# 5v_negative_and_positive_channels.net
KiCad netlist of a schematic drawn in Altium Designer
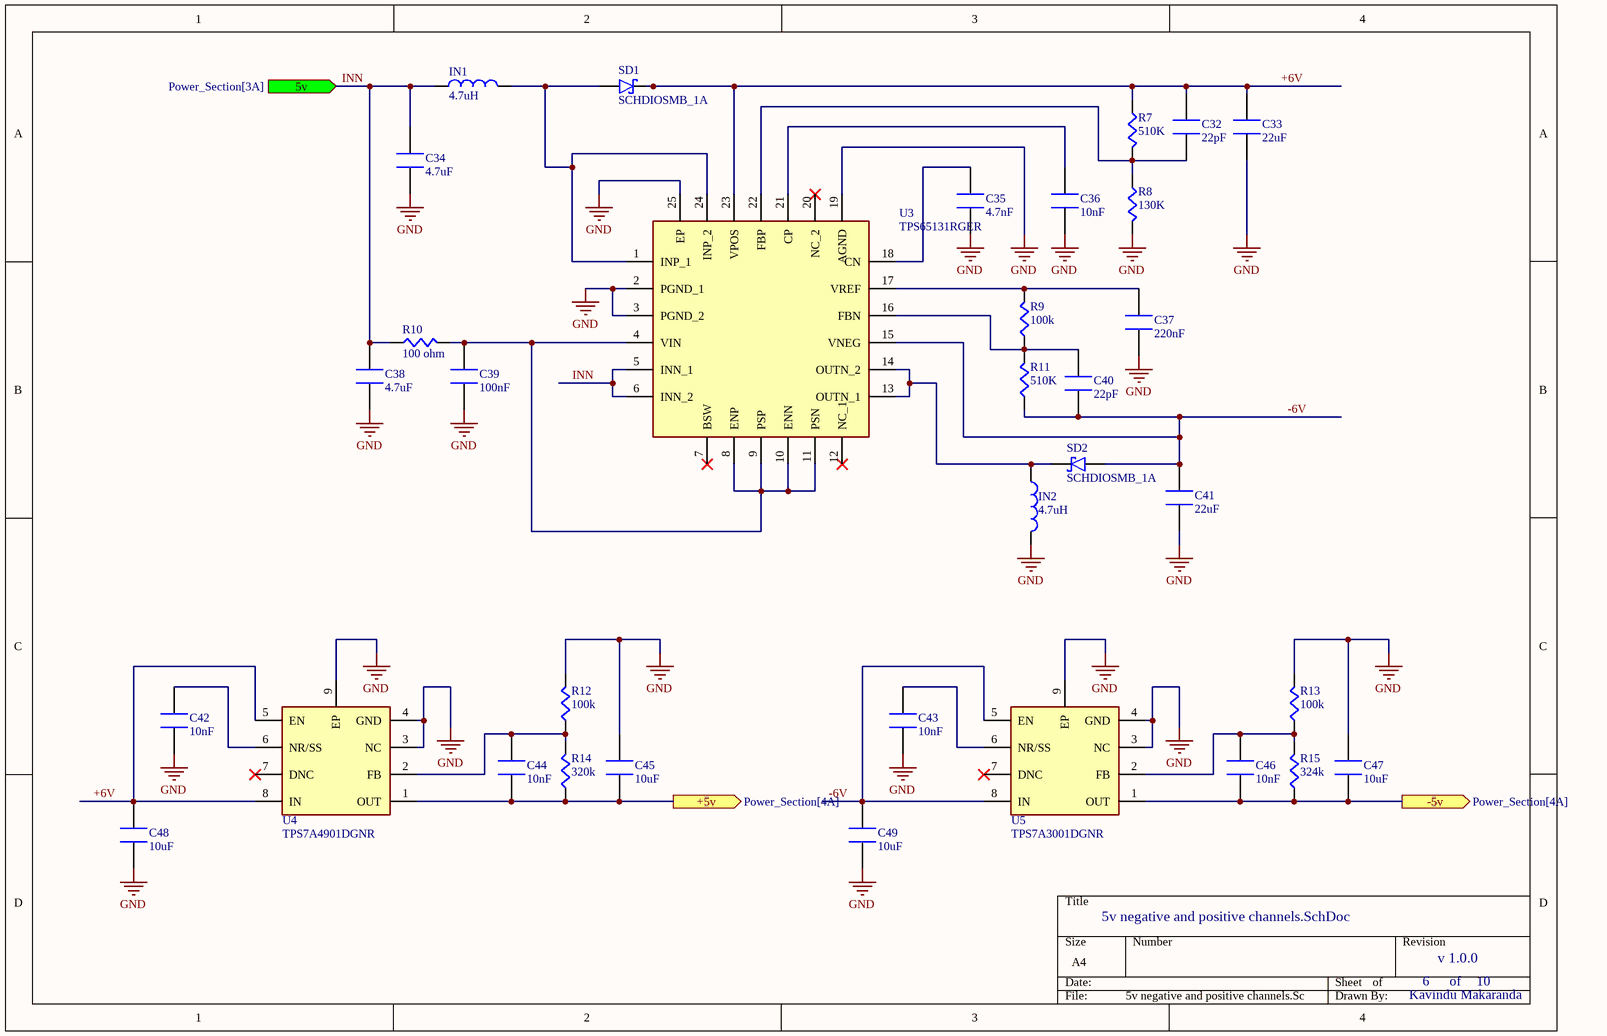
[diagram p0: 5v negative and positive channels.SchDoc]

(export (version "E")
  (design (tool "Eeschema 10.0.6"))
  (components
    (comp (ref "C32")
      (value "22pF")
      (footprint "CAPC0603X8N")
      (libsource (lib "Schlib1") (part "CC0603_22pF_NPO"))
    )
    (comp (ref "C33")
      (value "22uF")
      (footprint "CAPC1210X25N")
      (description "C309062, CL32B226KAJNNNE, 22uF 25V X7R ±10% 1210 Multilayer Ceramic Capacitors MLCC - SMD/SMT ROHS")
      (libsource (lib "Schlib1") (part "CC1210_22uF_X7R"))
    )
    (comp (ref "C34")
      (value "4.7uF")
      (footprint "CAP0805X13N")
      (libsource (lib "Schlib1") (part "CC0805_4.7uF_X7R"))
    )
    (comp (ref "C35")
      (value "4.7nF")
      (footprint "CAPC0603X8N")
      (libsource (lib "Schlib1") (part "CC0603_4.7nF_X7R"))
    )
    (comp (ref "C36")
      (value "10nF")
      (footprint "CAPC0603X8N")
      (libsource (lib "Schlib1") (part "CC0603_10nF_X7R"))
    )
    (comp (ref "C37")
      (value "220nF")
      (footprint "CAPC1206X18N")
      (libsource (lib "Schlib1") (part "CC0603_220nF_NPO"))
    )
    (comp (ref "C38")
      (value "4.7uF")
      (footprint "CAP0805X13N")
      (libsource (lib "Schlib1") (part "CC0805_4.7uF_X7R"))
    )
    (comp (ref "C39")
      (value "100nF")
      (footprint "CAPC0603X8N")
      (libsource (lib "Schlib1") (part "CC0603_100nF_X7R"))
    )
    (comp (ref "C40")
      (value "22pF")
      (footprint "CAPC0603X8N")
      (libsource (lib "Schlib1") (part "CC0603_22pF_NPO"))
    )
    (comp (ref "C41")
      (value "22uF")
      (footprint "CAPC1210X25N")
      (description "C309062, CL32B226KAJNNNE, 22uF 25V X7R ±10% 1210 Multilayer Ceramic Capacitors MLCC - SMD/SMT ROHS")
      (libsource (lib "Schlib1") (part "CC1210_22uF_X7R"))
    )
    (comp (ref "C42")
      (value "10nF")
      (footprint "CAPC0603X8N")
      (libsource (lib "Schlib1") (part "CC0603_10nF_X7R"))
    )
    (comp (ref "C43")
      (value "10nF")
      (footprint "CAPC0603X8N")
      (libsource (lib "Schlib1") (part "CC0603_10nF_X7R"))
    )
    (comp (ref "C44")
      (value "10nF")
      (footprint "CAPC0603X8N")
      (libsource (lib "Schlib1") (part "CC0603_10nF_X7R"))
    )
    (comp (ref "C45")
      (value "10uF")
      (footprint "CAPC0805X14N")
      (description "C95841, CL21B106KOQNNNE, 10uF 16V X7R ±10% 0805 Multilayer Ceramic Capacitors MLCC - SMD/SMT ROHS")
      (libsource (lib "Schlib1") (part "CC0805_10uF_X7R"))
    )
    (comp (ref "C46")
      (value "10nF")
      (footprint "CAPC0603X8N")
      (libsource (lib "Schlib1") (part "CC0603_10nF_X7R"))
    )
    (comp (ref "C47")
      (value "10uF")
      (footprint "CAPC0805X14N")
      (description "C95841, CL21B106KOQNNNE, 10uF 16V X7R ±10% 0805 Multilayer Ceramic Capacitors MLCC - SMD/SMT ROHS")
      (libsource (lib "Schlib1") (part "CC0805_10uF_X7R"))
    )
    (comp (ref "C48")
      (value "10uF")
      (footprint "CAPC0805X14N")
      (description "C95841, CL21B106KOQNNNE, 10uF 16V X7R ±10% 0805 Multilayer Ceramic Capacitors MLCC - SMD/SMT ROHS")
      (libsource (lib "Schlib1") (part "CC0805_10uF_X7R"))
    )
    (comp (ref "C49")
      (value "10uF")
      (footprint "CAPC0805X14N")
      (description "C95841, CL21B106KOQNNNE, 10uF 16V X7R ±10% 0805 Multilayer Ceramic Capacitors MLCC - SMD/SMT ROHS")
      (libsource (lib "Schlib1") (part "CC0805_10uF_X7R"))
    )
    (comp (ref "IN1")
      (value "4.7uH")
      (footprint "INDC2520X10N")
      (description "C91237, MLP2520S4R7MT0S1, 130mΩ 1A 4.7uH Multilayer inductor ±20% 1008 Inductors (SMD) ROHS")
      (libsource (lib "Schlib1") (part "IN2520_4.7uH_1A"))
    )
    (comp (ref "IN2")
      (value "4.7uH")
      (footprint "INDC2520X10N")
      (description "C91237, MLP2520S4R7MT0S1, 130mΩ 1A 4.7uH Multilayer inductor ±20% 1008 Inductors (SMD) ROHS")
      (libsource (lib "Schlib1") (part "IN2520_4.7uH_1A"))
    )
    (comp (ref "R7")
      (value "510K")
      (footprint "RECS0603X45N")
      (libsource (lib "Schlib1") (part "RESC0603_510K_THICK"))
    )
    (comp (ref "R8")
      (value "130K")
      (footprint "RECS0603X45N")
      (libsource (lib "Schlib1") (part "RESC0603_130K_THICK"))
    )
    (comp (ref "R9")
      (value "100k")
      (footprint "RECS0603X45N")
      (libsource (lib "Schlib1") (part "RESC0603_100K_THIN"))
    )
    (comp (ref "R10")
      (value "100 ohm")
      (footprint "RECS0603X45N")
      (libsource (lib "Schlib1") (part "RESC0603_100_THIN"))
    )
    (comp (ref "R11")
      (value "510K")
      (footprint "RECS0603X45N")
      (libsource (lib "Schlib1") (part "RESC0603_510K_THICK"))
    )
    (comp (ref "R12")
      (value "100k")
      (footprint "RECS0603X45N")
      (libsource (lib "Schlib1") (part "RESC0603_100K_THIN"))
    )
    (comp (ref "R13")
      (value "100k")
      (footprint "RECS0603X45N")
      (libsource (lib "Schlib1") (part "RESC0603_100K_THIN"))
    )
    (comp (ref "R14")
      (value "320k")
      (footprint "RECS0603X45N")
      (libsource (lib "Schlib1") (part "RESC0603_320K_THIN"))
    )
    (comp (ref "R15")
      (value "324k")
      (footprint "RECS0603X45N")
      (libsource (lib "Schlib1") (part "RESC0603_324K_THIN"))
    )
    (comp (ref "SD1")
      (value "SCHDIOSMB_1A")
      (footprint "SD_SMB_1A")
      (description "C86598, STPS160U, 1 Independent 1A 4uA@60V 60V 670mV@1A 75A SMB Schottky Diodes ROHS")
      (libsource (lib "Schlib1") (part "SCHDIOSMB_1A"))
    )
    (comp (ref "SD2")
      (value "SCHDIOSMB_1A")
      (footprint "SD_SMB_1A")
      (description "C86598, STPS160U, 1 Independent 1A 4uA@60V 60V 670mV@1A 75A SMB Schottky Diodes ROHS")
      (libsource (lib "Schlib1") (part "SCHDIOSMB_1A"))
    )
    (comp (ref "U3")
      (value "TPS65131RGER")
      (footprint "QFN50P400X400X100-25N-D")
      (fields (field (name "MOUSER PART NUMBER") "595-TPS65131RGER"))
      (libsource (lib "Schlib1") (part "TPS65131RGER"))
    )
    (comp (ref "U4")
      (value "TPS7A4901DGNR")
      (footprint "SOP65P490X110-9N")
      (fields (field (name "MOUSER PART NUMBER") "595-TPS7A4901DGNR"))
      (libsource (lib "Schlib1") (part "TPS7A4901DGNR"))
    )
    (comp (ref "U5")
      (value "TPS7A3001DGNR")
      (footprint "SOP65P490X110-9N")
      (fields (field (name "MOUSER PART NUMBER") "595-TPS7A3001DGNR"))
      (libsource (lib "Schlib1") (part "TPS7A3001DGNR"))
    )
  )
  (nets
    (net (code "1") (name "/+5v") (class "Default")
      (node (ref "C44") (pin "1") (pinfunction "1_1") (pintype "passive"))
      (node (ref "C45") (pin "1") (pinfunction "1_1") (pintype "passive"))
      (node (ref "R14") (pin "1") (pinfunction "1_1") (pintype "passive"))
      (node (ref "U4") (pin "1") (pinfunction "OUT_1") (pintype "passive"))
    )
    (net (code "2") (name "/+6V") (class "Default")
      (node (ref "C32") (pin "2") (pinfunction "2_2") (pintype "passive"))
      (node (ref "C33") (pin "2") (pinfunction "2_2") (pintype "passive"))
      (node (ref "C48") (pin "2") (pinfunction "2_2") (pintype "passive"))
      (node (ref "R7") (pin "1") (pinfunction "1_1") (pintype "passive"))
      (node (ref "SD1") (pin "2") (pinfunction "2_2") (pintype "passive"))
      (node (ref "U3") (pin "23") (pinfunction "VPOS_23") (pintype "passive"))
      (node (ref "U4") (pin "5") (pinfunction "EN_5") (pintype "passive"))
      (node (ref "U4") (pin "8") (pinfunction "IN_8") (pintype "passive"))
    )
    (net (code "3") (name "/-5v") (class "Default")
      (node (ref "C46") (pin "1") (pinfunction "1_1") (pintype "passive"))
      (node (ref "C47") (pin "1") (pinfunction "1_1") (pintype "passive"))
      (node (ref "R15") (pin "1") (pinfunction "1_1") (pintype "passive"))
      (node (ref "U5") (pin "1") (pinfunction "OUT_1") (pintype "passive"))
    )
    (net (code "4") (name "/-6V") (class "Default")
      (node (ref "C40") (pin "1") (pinfunction "1_1") (pintype "passive"))
      (node (ref "C41") (pin "2") (pinfunction "2_2") (pintype "passive"))
      (node (ref "C49") (pin "2") (pinfunction "2_2") (pintype "passive"))
      (node (ref "R11") (pin "1") (pinfunction "1_1") (pintype "passive"))
      (node (ref "SD2") (pin "1") (pinfunction "1_1") (pintype "passive"))
      (node (ref "U3") (pin "15") (pinfunction "VNEG_15") (pintype "passive"))
      (node (ref "U5") (pin "5") (pinfunction "EN_5") (pintype "passive"))
      (node (ref "U5") (pin "8") (pinfunction "IN_8") (pintype "passive"))
    )
    (net (code "5") (name "/INN") (class "Default")
      (node (ref "C34") (pin "2") (pinfunction "2_2") (pintype "passive"))
      (node (ref "C38") (pin "2") (pinfunction "2_2") (pintype "passive"))
      (node (ref "IN1") (pin "1") (pinfunction "1_1") (pintype "passive"))
      (node (ref "R10") (pin "1") (pinfunction "1_1") (pintype "passive"))
      (node (ref "U3") (pin "5") (pinfunction "INN_1_5") (pintype "passive"))
      (node (ref "U3") (pin "6") (pinfunction "INN_2_6") (pintype "passive"))
    )
    (net (code "6") (name "GND") (class "Default")
      (node (ref "C33") (pin "1") (pinfunction "1_1") (pintype "passive"))
      (node (ref "C34") (pin "1") (pinfunction "1_1") (pintype "passive"))
      (node (ref "C35") (pin "1") (pinfunction "1_1") (pintype "passive"))
      (node (ref "C36") (pin "1") (pinfunction "1_1") (pintype "passive"))
      (node (ref "C37") (pin "1") (pinfunction "1_1") (pintype "passive"))
      (node (ref "C38") (pin "1") (pinfunction "1_1") (pintype "passive"))
      (node (ref "C39") (pin "1") (pinfunction "1_1") (pintype "passive"))
      (node (ref "C41") (pin "1") (pinfunction "1_1") (pintype "passive"))
      (node (ref "C42") (pin "1") (pinfunction "1_1") (pintype "passive"))
      (node (ref "C43") (pin "1") (pinfunction "1_1") (pintype "passive"))
      (node (ref "C45") (pin "2") (pinfunction "2_2") (pintype "passive"))
      (node (ref "C47") (pin "2") (pinfunction "2_2") (pintype "passive"))
      (node (ref "C48") (pin "1") (pinfunction "1_1") (pintype "passive"))
      (node (ref "C49") (pin "1") (pinfunction "1_1") (pintype "passive"))
      (node (ref "IN2") (pin "2") (pinfunction "2_2") (pintype "passive"))
      (node (ref "R12") (pin "2") (pinfunction "2_2") (pintype "passive"))
      (node (ref "R13") (pin "2") (pinfunction "2_2") (pintype "passive"))
      (node (ref "R8") (pin "2") (pinfunction "2_2") (pintype "passive"))
      (node (ref "U3") (pin "19") (pinfunction "AGND_19") (pintype "passive"))
      (node (ref "U3") (pin "2") (pinfunction "PGND_1_2") (pintype "passive"))
      (node (ref "U3") (pin "25") (pinfunction "EP_25") (pintype "passive"))
      (node (ref "U3") (pin "3") (pinfunction "PGND_2_3") (pintype "passive"))
      (node (ref "U4") (pin "3") (pinfunction "NC_3") (pintype "passive"))
      (node (ref "U4") (pin "4") (pinfunction "GND_4") (pintype "passive"))
      (node (ref "U4") (pin "9") (pinfunction "EP_9") (pintype "passive"))
      (node (ref "U5") (pin "3") (pinfunction "NC_3") (pintype "passive"))
      (node (ref "U5") (pin "4") (pinfunction "GND_4") (pintype "passive"))
      (node (ref "U5") (pin "9") (pinfunction "EP_9") (pintype "passive"))
    )
    (net (code "7") (name "Net-(U3-CN)") (class "Default")
      (node (ref "C35") (pin "2") (pinfunction "2_2") (pintype "passive"))
      (node (ref "U3") (pin "18") (pinfunction "CN_18") (pintype "passive"))
    )
    (net (code "8") (name "Net-(U3-CP)") (class "Default")
      (node (ref "C36") (pin "2") (pinfunction "2_2") (pintype "passive"))
      (node (ref "U3") (pin "21") (pinfunction "CP_21") (pintype "passive"))
    )
    (net (code "9") (name "Net-(U3-ENN)") (class "Default")
      (node (ref "C39") (pin "2") (pinfunction "2_2") (pintype "passive"))
      (node (ref "R10") (pin "2") (pinfunction "2_2") (pintype "passive"))
      (node (ref "U3") (pin "10") (pinfunction "ENN_10") (pintype "passive"))
      (node (ref "U3") (pin "11") (pinfunction "PSN_11") (pintype "passive"))
      (node (ref "U3") (pin "4") (pinfunction "VIN_4") (pintype "passive"))
      (node (ref "U3") (pin "8") (pinfunction "ENP_8") (pintype "passive"))
      (node (ref "U3") (pin "9") (pinfunction "PSP_9") (pintype "passive"))
    )
    (net (code "10") (name "Net-(U3-FBN)") (class "Default")
      (node (ref "C40") (pin "2") (pinfunction "2_2") (pintype "passive"))
      (node (ref "R11") (pin "2") (pinfunction "2_2") (pintype "passive"))
      (node (ref "R9") (pin "1") (pinfunction "1_1") (pintype "passive"))
      (node (ref "U3") (pin "16") (pinfunction "FBN_16") (pintype "passive"))
    )
    (net (code "11") (name "Net-(U3-FBP)") (class "Default")
      (node (ref "C32") (pin "1") (pinfunction "1_1") (pintype "passive"))
      (node (ref "R7") (pin "2") (pinfunction "2_2") (pintype "passive"))
      (node (ref "R8") (pin "1") (pinfunction "1_1") (pintype "passive"))
      (node (ref "U3") (pin "22") (pinfunction "FBP_22") (pintype "passive"))
    )
    (net (code "12") (name "Net-(U3-INP_1)") (class "Default")
      (node (ref "IN1") (pin "2") (pinfunction "2_2") (pintype "passive"))
      (node (ref "SD1") (pin "1") (pinfunction "1_1") (pintype "passive"))
      (node (ref "U3") (pin "1") (pinfunction "INP_1_1") (pintype "passive"))
      (node (ref "U3") (pin "24") (pinfunction "INP_2_24") (pintype "passive"))
    )
    (net (code "13") (name "Net-(U3-OUTN_1)") (class "Default")
      (node (ref "IN2") (pin "1") (pinfunction "1_1") (pintype "passive"))
      (node (ref "SD2") (pin "2") (pinfunction "2_2") (pintype "passive"))
      (node (ref "U3") (pin "13") (pinfunction "OUTN_1_13") (pintype "passive"))
      (node (ref "U3") (pin "14") (pinfunction "OUTN_2_14") (pintype "passive"))
    )
    (net (code "14") (name "Net-(U3-VREF)") (class "Default")
      (node (ref "C37") (pin "2") (pinfunction "2_2") (pintype "passive"))
      (node (ref "R9") (pin "2") (pinfunction "2_2") (pintype "passive"))
      (node (ref "U3") (pin "17") (pinfunction "VREF_17") (pintype "passive"))
    )
    (net (code "15") (name "Net-(U4-FB)") (class "Default")
      (node (ref "C44") (pin "2") (pinfunction "2_2") (pintype "passive"))
      (node (ref "R12") (pin "1") (pinfunction "1_1") (pintype "passive"))
      (node (ref "R14") (pin "2") (pinfunction "2_2") (pintype "passive"))
      (node (ref "U4") (pin "2") (pinfunction "FB_2") (pintype "passive"))
    )
    (net (code "16") (name "Net-(U4-NR{slash}SS)") (class "Default")
      (node (ref "C42") (pin "2") (pinfunction "2_2") (pintype "passive"))
      (node (ref "U4") (pin "6") (pinfunction "NR/SS_6") (pintype "passive"))
    )
    (net (code "17") (name "Net-(U5-FB)") (class "Default")
      (node (ref "C46") (pin "2") (pinfunction "2_2") (pintype "passive"))
      (node (ref "R13") (pin "1") (pinfunction "1_1") (pintype "passive"))
      (node (ref "R15") (pin "2") (pinfunction "2_2") (pintype "passive"))
      (node (ref "U5") (pin "2") (pinfunction "FB_2") (pintype "passive"))
    )
    (net (code "18") (name "Net-(U5-NR{slash}SS)") (class "Default")
      (node (ref "C43") (pin "2") (pinfunction "2_2") (pintype "passive"))
      (node (ref "U5") (pin "6") (pinfunction "NR/SS_6") (pintype "passive"))
    )
    (net (code "19") (name "unconnected-(U3-BSW-Pad7)") (class "Default")
      (node (ref "U3") (pin "7") (pinfunction "BSW_7") (pintype "passive+no_connect"))
    )
    (net (code "20") (name "unconnected-(U3-NC_1-Pad12)") (class "Default")
      (node (ref "U3") (pin "12") (pinfunction "NC_1_12") (pintype "passive+no_connect"))
    )
    (net (code "21") (name "unconnected-(U3-NC_2-Pad20)") (class "Default")
      (node (ref "U3") (pin "20") (pinfunction "NC_2_20") (pintype "passive+no_connect"))
    )
    (net (code "22") (name "unconnected-(U4-DNC-Pad7)") (class "Default")
      (node (ref "U4") (pin "7") (pinfunction "DNC_7") (pintype "passive+no_connect"))
    )
    (net (code "23") (name "unconnected-(U5-DNC-Pad7)") (class "Default")
      (node (ref "U5") (pin "7") (pinfunction "DNC_7") (pintype "passive+no_connect"))
    )
  )
)
